# Commutator_Adaptor.net
KiCad netlist of a schematic drawn in EAGLE
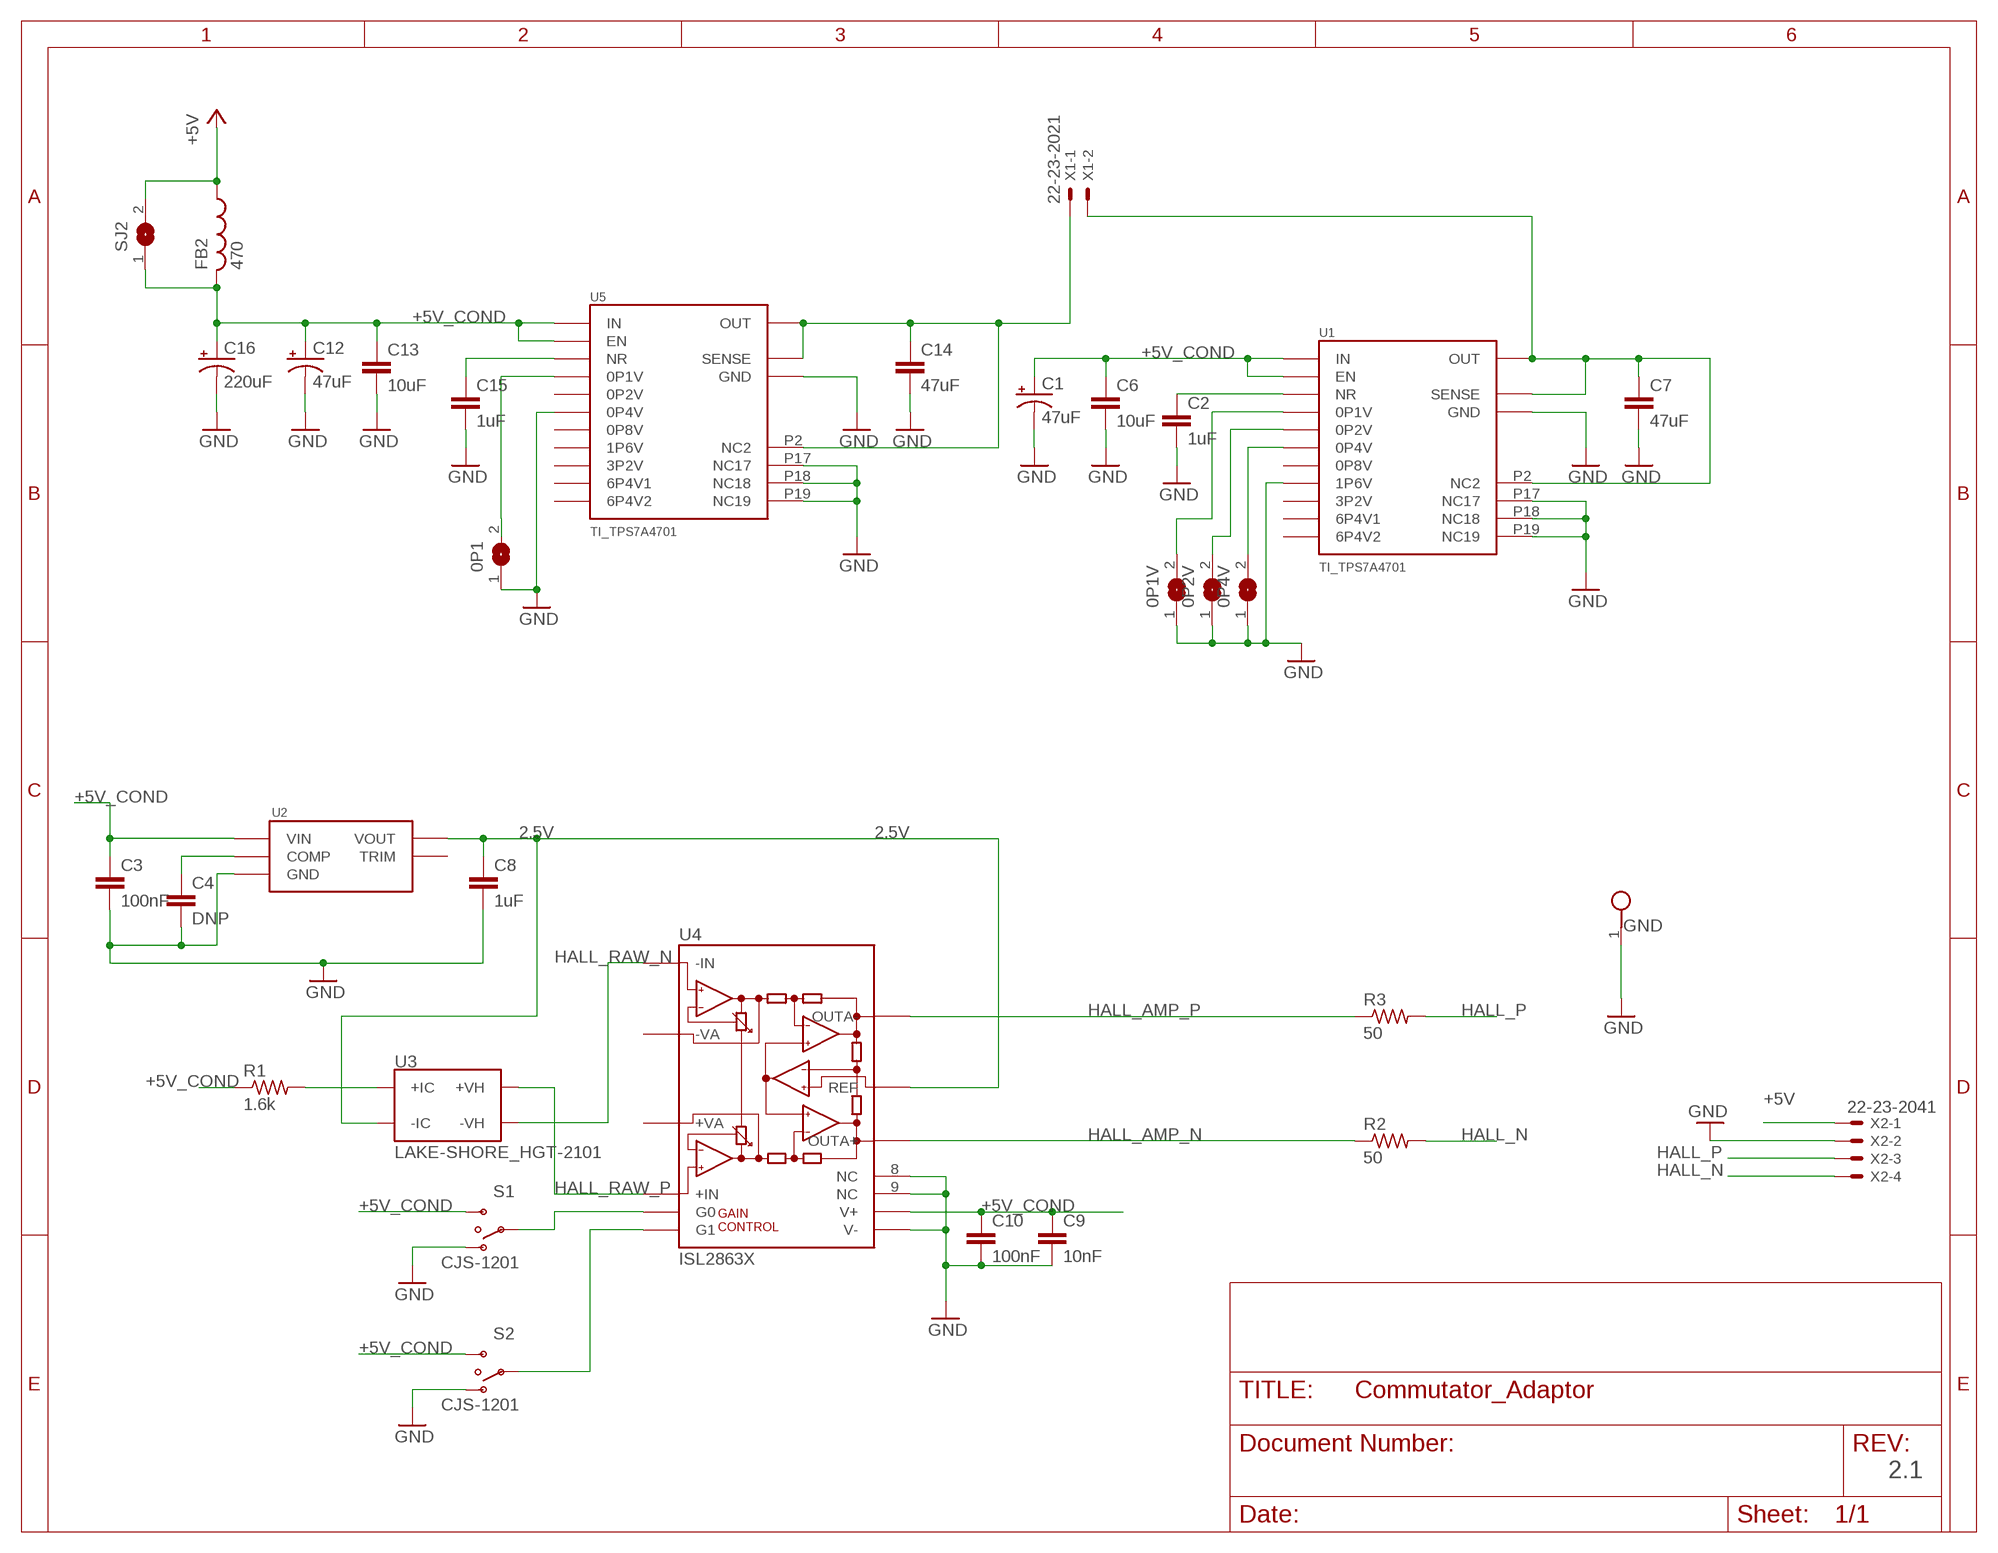
[diagram p0: schematic, sheet 1]

(export (version "E")
  (design (tool "Eeschema 10.0.6"))
  (components
    (comp (ref "0P1") (value "SJ") (footprint "eagle-import:SJ") (libsource (lib "eagle-import") (part "SJ")))
    (comp (ref "0P1V")
      (value "SJ")
      (footprint "eagle-import:SJ")
      (libsource (lib "eagle-import") (part "SJ"))
    )
    (comp (ref "0P2V")
      (value "SJ")
      (footprint "eagle-import:SJ")
      (libsource (lib "eagle-import") (part "SJ"))
    )
    (comp (ref "0P4V")
      (value "SJ")
      (footprint "eagle-import:SJ")
      (libsource (lib "eagle-import") (part "SJ"))
    )
    (comp (ref "C1")
      (value "47uF")
      (footprint "eagle-import:1210POL")
      (libsource (lib "eagle-import") (part "CPOL1210"))
    )
    (comp (ref "C2")
      (value "1uF")
      (footprint "eagle-import:0603")
      (libsource (lib "eagle-import") (part "C_0603"))
    )
    (comp (ref "C3")
      (value "100nF")
      (footprint "eagle-import:0402")
      (libsource (lib "eagle-import") (part "C_0402"))
    )
    (comp (ref "C4")
      (value "DNP")
      (footprint "eagle-import:0402")
      (libsource (lib "eagle-import") (part "C_0402"))
    )
    (comp (ref "C6")
      (value "10uF")
      (footprint "eagle-import:0805")
      (libsource (lib "eagle-import") (part "C_0805"))
    )
    (comp (ref "C7")
      (value "47uF")
      (footprint "eagle-import:1210")
      (libsource (lib "eagle-import") (part "C_1210"))
    )
    (comp (ref "C8")
      (value "1uF")
      (footprint "eagle-import:0603")
      (libsource (lib "eagle-import") (part "C_0603"))
    )
    (comp (ref "C9")
      (value "10nF")
      (footprint "eagle-import:0402")
      (libsource (lib "eagle-import") (part "C_0402"))
    )
    (comp (ref "C10")
      (value "100nF")
      (footprint "eagle-import:0402")
      (libsource (lib "eagle-import") (part "C_0402"))
    )
    (comp (ref "C12")
      (value "47uF")
      (footprint "eagle-import:1210POL")
      (libsource (lib "eagle-import") (part "CPOL1210"))
    )
    (comp (ref "C13")
      (value "10uF")
      (footprint "eagle-import:0805")
      (libsource (lib "eagle-import") (part "C_0805"))
    )
    (comp (ref "C14")
      (value "47uF")
      (footprint "eagle-import:1210")
      (libsource (lib "eagle-import") (part "C_1210"))
    )
    (comp (ref "C15")
      (value "1uF")
      (footprint "eagle-import:0603")
      (libsource (lib "eagle-import") (part "C_0603"))
    )
    (comp (ref "C16")
      (value "220uF")
      (footprint "eagle-import:JA0")
      (libsource (lib "eagle-import") (part "CPOL_JA0"))
    )
    (comp (ref "FB2")
      (value "470")
      (footprint "eagle-import:0603")
      (libsource (lib "eagle-import") (part "L_0603"))
    )
    (comp (ref "GND")
      (value "TESTPOINT_SMALL")
      (footprint "eagle-import:TESTPOINT_SMALL")
      (libsource (lib "eagle-import") (part "TESTPOINT_SMALL"))
    )
    (comp (ref "R1")
      (value "1.6k")
      (footprint "eagle-import:0402")
      (libsource (lib "eagle-import") (part "R_0402"))
    )
    (comp (ref "R2")
      (value "50")
      (footprint "eagle-import:0402")
      (libsource (lib "eagle-import") (part "R_0402"))
    )
    (comp (ref "R3")
      (value "50")
      (footprint "eagle-import:0402")
      (libsource (lib "eagle-import") (part "R_0402"))
    )
    (comp (ref "S1")
      (value "CJS-1201")
      (footprint "eagle-import:CJS-1201A1")
      (libsource (lib "eagle-import") (part "CJS-1201"))
    )
    (comp (ref "S2")
      (value "CJS-1201")
      (footprint "eagle-import:CJS-1201A1")
      (libsource (lib "eagle-import") (part "CJS-1201"))
    )
    (comp (ref "SJ2") (value "SJ") (footprint "eagle-import:SJ") (libsource (lib "eagle-import") (part "SJ")))
    (comp (ref "U1")
      (value "TI_TPS7A4701")
      (footprint "eagle-import:20-VQFN(5X5)")
      (libsource (lib "eagle-import") (part "TI_TPS7A4701"))
    )
    (comp (ref "U2")
      (value "ISL21090")
      (footprint "eagle-import:SO08")
      (libsource (lib "eagle-import") (part "ISL21090"))
    )
    (comp (ref "U3")
      (value "LAKE-SHORE_HGT-2101")
      (footprint "eagle-import:HGT-2101-SIDE")
      (libsource (lib "eagle-import") (part "LAKE-SHORE_HGT-2101"))
    )
    (comp (ref "U4")
      (value "ISL2863X")
      (footprint "eagle-import:TSSOP14")
      (libsource (lib "eagle-import") (part "ISL2863X"))
    )
    (comp (ref "U5")
      (value "TI_TPS7A4701")
      (footprint "eagle-import:20-VQFN(5X5)")
      (libsource (lib "eagle-import") (part "TI_TPS7A4701"))
    )
    (comp (ref "X1")
      (value "22-23-2021")
      (footprint "eagle-import:22-23-2021")
      (fields (field (name "MF") "MOLEX"))
      (libsource (lib "eagle-import") (part "22-23-2021"))
    )
    (comp (ref "X2")
      (value "22-23-2041")
      (footprint "eagle-import:22-23-2041")
      (fields (field (name "MF") "MOLEX"))
      (libsource (lib "eagle-import") (part "22-23-2041"))
    )
  )
  (nets
    (net (code "1") (name "+5V") (class "Default")
      (node (ref "FB2") (pin "1") (pinfunction "1_1") (pintype "passive"))
      (node (ref "SJ2") (pin "2") (pinfunction "2_2") (pintype "passive"))
      (node (ref "X2") (pin "1") (pinfunction "S_1") (pintype "passive"))
    )
    (net (code "2") (name "/+5V_COND") (class "Default")
      (node (ref "C1") (pin "POS") (pinfunction "+_POS") (pintype "passive"))
      (node (ref "C10") (pin "1") (pinfunction "1_1") (pintype "passive"))
      (node (ref "C12") (pin "POS") (pinfunction "+_POS") (pintype "passive"))
      (node (ref "C13") (pin "1") (pinfunction "1_1") (pintype "passive"))
      (node (ref "C16") (pin "POS") (pinfunction "+_POS") (pintype "passive"))
      (node (ref "C3") (pin "1") (pinfunction "1_1") (pintype "passive"))
      (node (ref "C6") (pin "1") (pinfunction "1_1") (pintype "passive"))
      (node (ref "C9") (pin "1") (pinfunction "1_1") (pintype "passive"))
      (node (ref "FB2") (pin "2") (pinfunction "2_2") (pintype "passive"))
      (node (ref "R1") (pin "1") (pinfunction "1_1") (pintype "passive"))
      (node (ref "S1") (pin "P$3") (pinfunction "S_P$3") (pintype "passive"))
      (node (ref "S2") (pin "P$3") (pinfunction "S_P$3") (pintype "passive"))
      (node (ref "SJ2") (pin "1") (pinfunction "1_1") (pintype "passive"))
      (node (ref "U1") (pin "P13") (pinfunction "EN_P13") (pintype "input"))
      (node (ref "U1") (pin "P15") (pinfunction "IN_P15") (pintype "power_in"))
      (node (ref "U1") (pin "P16") (pinfunction "IN_P16") (pintype "power_in"))
      (node (ref "U2") (pin "2") (pinfunction "VIN_2") (pintype "power_in"))
      (node (ref "U4") (pin "14") (pinfunction "V+_14") (pintype "power_in"))
      (node (ref "U5") (pin "P13") (pinfunction "EN_P13") (pintype "input"))
      (node (ref "U5") (pin "P15") (pinfunction "IN_P15") (pintype "power_in"))
      (node (ref "U5") (pin "P16") (pinfunction "IN_P16") (pintype "power_in"))
    )
    (net (code "3") (name "/2.5V") (class "Default")
      (node (ref "C8") (pin "1") (pinfunction "1_1") (pintype "passive"))
      (node (ref "U2") (pin "6") (pinfunction "VOUT_6") (pintype "power_in"))
      (node (ref "U3") (pin "PIN1") (pinfunction "-IC_PIN1") (pintype "power_in"))
      (node (ref "U4") (pin "11") (pinfunction "REF_11") (pintype "input"))
    )
    (net (code "4") (name "/HALL_AMP_N") (class "Default")
      (node (ref "R2") (pin "1") (pinfunction "1_1") (pintype "passive"))
      (node (ref "U4") (pin "12") (pinfunction "OUTA+_12") (pintype "passive"))
    )
    (net (code "5") (name "/HALL_AMP_P") (class "Default")
      (node (ref "R3") (pin "1") (pinfunction "1_1") (pintype "passive"))
      (node (ref "U4") (pin "10") (pinfunction "OUTA-_10") (pintype "output"))
    )
    (net (code "6") (name "/HALL_N") (class "Default")
      (node (ref "R2") (pin "2") (pinfunction "2_2") (pintype "passive"))
      (node (ref "X2") (pin "4") (pinfunction "S_4") (pintype "passive"))
    )
    (net (code "7") (name "/HALL_P") (class "Default")
      (node (ref "R3") (pin "2") (pinfunction "2_2") (pintype "passive"))
      (node (ref "X2") (pin "3") (pinfunction "S_3") (pintype "passive"))
    )
    (net (code "8") (name "/HALL_RAW_N") (class "Default")
      (node (ref "U3") (pin "WIRE1") (pinfunction "-VH_WIRE1") (pintype "output"))
      (node (ref "U4") (pin "5") (pinfunction "-IN_5") (pintype "input"))
    )
    (net (code "9") (name "/HALL_RAW_P") (class "Default")
      (node (ref "U3") (pin "PIN2") (pinfunction "+VH_PIN2") (pintype "output"))
      (node (ref "U4") (pin "4") (pinfunction "+IN_4") (pintype "input"))
    )
    (net (code "10") (name "GND") (class "Default")
      (node (ref "0P1") (pin "1") (pinfunction "1_1") (pintype "passive"))
      (node (ref "0P1V") (pin "1") (pinfunction "1_1") (pintype "passive"))
      (node (ref "0P2V") (pin "1") (pinfunction "1_1") (pintype "passive"))
      (node (ref "0P4V") (pin "1") (pinfunction "1_1") (pintype "passive"))
      (node (ref "C1") (pin "NEG") (pinfunction "-_NEG") (pintype "passive"))
      (node (ref "C10") (pin "2") (pinfunction "2_2") (pintype "passive"))
      (node (ref "C12") (pin "NEG") (pinfunction "-_NEG") (pintype "passive"))
      (node (ref "C13") (pin "2") (pinfunction "2_2") (pintype "passive"))
      (node (ref "C14") (pin "NEG") (pinfunction "2_NEG") (pintype "passive"))
      (node (ref "C15") (pin "2") (pinfunction "2_2") (pintype "passive"))
      (node (ref "C16") (pin "NEG") (pinfunction "-_NEG") (pintype "passive"))
      (node (ref "C2") (pin "2") (pinfunction "2_2") (pintype "passive"))
      (node (ref "C3") (pin "2") (pinfunction "2_2") (pintype "passive"))
      (node (ref "C4") (pin "2") (pinfunction "2_2") (pintype "passive"))
      (node (ref "C6") (pin "2") (pinfunction "2_2") (pintype "passive"))
      (node (ref "C7") (pin "NEG") (pinfunction "2_NEG") (pintype "passive"))
      (node (ref "C8") (pin "2") (pinfunction "2_2") (pintype "passive"))
      (node (ref "C9") (pin "2") (pinfunction "2_2") (pintype "passive"))
      (node (ref "GND") (pin "1") (pinfunction "1_1") (pintype "passive"))
      (node (ref "S1") (pin "P$1") (pinfunction "O_P$1") (pintype "passive"))
      (node (ref "S2") (pin "P$1") (pinfunction "O_P$1") (pintype "passive"))
      (node (ref "U1") (pin "P17") (pinfunction "NC17_P17") (pintype "passive"))
      (node (ref "U1") (pin "P18") (pinfunction "NC18_P18") (pintype "passive"))
      (node (ref "U1") (pin "P19") (pinfunction "NC19_P19") (pintype "passive"))
      (node (ref "U1") (pin "P7") (pinfunction "GND_P7") (pintype "power_in"))
      (node (ref "U1") (pin "P8") (pinfunction "1P6V_P8") (pintype "passive"))
      (node (ref "U1") (pin "THERMAL@1") (pinfunction "GND_THERMAL@1") (pintype "power_in"))
      (node (ref "U1") (pin "THERMAL@10") (pinfunction "GND_THERMAL@10") (pintype "power_in"))
      (node (ref "U1") (pin "THERMAL@2") (pinfunction "GND_THERMAL@2") (pintype "power_in"))
      (node (ref "U1") (pin "THERMAL@3") (pinfunction "GND_THERMAL@3") (pintype "power_in"))
      (node (ref "U1") (pin "THERMAL@4") (pinfunction "GND_THERMAL@4") (pintype "power_in"))
      (node (ref "U1") (pin "THERMAL@5") (pinfunction "GND_THERMAL@5") (pintype "power_in"))
      (node (ref "U1") (pin "THERMAL@6") (pinfunction "GND_THERMAL@6") (pintype "power_in"))
      (node (ref "U1") (pin "THERMAL@7") (pinfunction "GND_THERMAL@7") (pintype "power_in"))
      (node (ref "U1") (pin "THERMAL@8") (pinfunction "GND_THERMAL@8") (pintype "power_in"))
      (node (ref "U1") (pin "THERMAL@9") (pinfunction "GND_THERMAL@9") (pintype "power_in"))
      (node (ref "U2") (pin "4") (pinfunction "GND_4") (pintype "power_in"))
      (node (ref "U4") (pin "7") (pinfunction "V-_7") (pintype "power_in"))
      (node (ref "U4") (pin "8") (pinfunction "NC_8") (pintype "passive"))
      (node (ref "U4") (pin "9") (pinfunction "NC_9") (pintype "passive"))
      (node (ref "U5") (pin "P10") (pinfunction "0P4V_P10") (pintype "passive"))
      (node (ref "U5") (pin "P17") (pinfunction "NC17_P17") (pintype "passive"))
      (node (ref "U5") (pin "P18") (pinfunction "NC18_P18") (pintype "passive"))
      (node (ref "U5") (pin "P19") (pinfunction "NC19_P19") (pintype "passive"))
      (node (ref "U5") (pin "P7") (pinfunction "GND_P7") (pintype "power_in"))
      (node (ref "U5") (pin "THERMAL@1") (pinfunction "GND_THERMAL@1") (pintype "power_in"))
      (node (ref "U5") (pin "THERMAL@10") (pinfunction "GND_THERMAL@10") (pintype "power_in"))
      (node (ref "U5") (pin "THERMAL@2") (pinfunction "GND_THERMAL@2") (pintype "power_in"))
      (node (ref "U5") (pin "THERMAL@3") (pinfunction "GND_THERMAL@3") (pintype "power_in"))
      (node (ref "U5") (pin "THERMAL@4") (pinfunction "GND_THERMAL@4") (pintype "power_in"))
      (node (ref "U5") (pin "THERMAL@5") (pinfunction "GND_THERMAL@5") (pintype "power_in"))
      (node (ref "U5") (pin "THERMAL@6") (pinfunction "GND_THERMAL@6") (pintype "power_in"))
      (node (ref "U5") (pin "THERMAL@7") (pinfunction "GND_THERMAL@7") (pintype "power_in"))
      (node (ref "U5") (pin "THERMAL@8") (pinfunction "GND_THERMAL@8") (pintype "power_in"))
      (node (ref "U5") (pin "THERMAL@9") (pinfunction "GND_THERMAL@9") (pintype "power_in"))
      (node (ref "X2") (pin "2") (pinfunction "S_2") (pintype "passive"))
    )
    (net (code "11") (name "Net-(C7-1)") (class "Default")
      (node (ref "C7") (pin "POS") (pinfunction "1_POS") (pintype "passive"))
      (node (ref "U1") (pin "P1") (pinfunction "OUT_P1") (pintype "power_in"))
      (node (ref "U1") (pin "P2") (pinfunction "NC2_P2") (pintype "passive"))
      (node (ref "U1") (pin "P20") (pinfunction "OUT_P20") (pintype "power_in"))
      (node (ref "U1") (pin "P3") (pinfunction "SENSE_P3") (pintype "input"))
      (node (ref "X1") (pin "2") (pinfunction "S_2") (pintype "passive"))
    )
    (net (code "12") (name "Net-(C14-1)") (class "Default")
      (node (ref "C14") (pin "POS") (pinfunction "1_POS") (pintype "passive"))
      (node (ref "U5") (pin "P1") (pinfunction "OUT_P1") (pintype "power_in"))
      (node (ref "U5") (pin "P2") (pinfunction "NC2_P2") (pintype "passive"))
      (node (ref "U5") (pin "P20") (pinfunction "OUT_P20") (pintype "power_in"))
      (node (ref "U5") (pin "P3") (pinfunction "SENSE_P3") (pintype "input"))
      (node (ref "X1") (pin "1") (pinfunction "S_1") (pintype "passive"))
    )
    (net (code "13") (name "Net-(S1-P)") (class "Default")
      (node (ref "S1") (pin "P$2") (pinfunction "P_P$2") (pintype "passive"))
      (node (ref "U4") (pin "1") (pinfunction "G0_1") (pintype "input"))
    )
    (net (code "14") (name "Net-(S2-P)") (class "Default")
      (node (ref "S2") (pin "P$2") (pinfunction "P_P$2") (pintype "passive"))
      (node (ref "U4") (pin "2") (pinfunction "G1_2") (pintype "input"))
    )
    (net (code "15") (name "Net-(U1-0P1V)") (class "Default")
      (node (ref "0P1V") (pin "2") (pinfunction "2_2") (pintype "passive"))
      (node (ref "U1") (pin "P12") (pinfunction "0P1V_P12") (pintype "passive"))
    )
    (net (code "16") (name "Net-(U1-0P2V)") (class "Default")
      (node (ref "0P2V") (pin "2") (pinfunction "2_2") (pintype "passive"))
      (node (ref "U1") (pin "P11") (pinfunction "0P2V_P11") (pintype "passive"))
    )
    (net (code "17") (name "Net-(U1-0P4V)") (class "Default")
      (node (ref "0P4V") (pin "2") (pinfunction "2_2") (pintype "passive"))
      (node (ref "U1") (pin "P10") (pinfunction "0P4V_P10") (pintype "passive"))
    )
    (net (code "18") (name "Net-(U1-NR)") (class "Default")
      (node (ref "C2") (pin "1") (pinfunction "1_1") (pintype "passive"))
      (node (ref "U1") (pin "P14") (pinfunction "NR_P14") (pintype "passive"))
    )
    (net (code "19") (name "Net-(U2-COMP)") (class "Default")
      (node (ref "C4") (pin "1") (pinfunction "1_1") (pintype "passive"))
      (node (ref "U2") (pin "3") (pinfunction "COMP_3") (pintype "output"))
    )
    (net (code "20") (name "Net-(U3-+IC)") (class "Default")
      (node (ref "R1") (pin "2") (pinfunction "2_2") (pintype "passive"))
      (node (ref "U3") (pin "WIRE2") (pinfunction "+IC_WIRE2") (pintype "power_in"))
    )
    (net (code "21") (name "Net-(U5-0P1V)") (class "Default")
      (node (ref "0P1") (pin "2") (pinfunction "2_2") (pintype "passive"))
      (node (ref "U5") (pin "P12") (pinfunction "0P1V_P12") (pintype "passive"))
    )
    (net (code "22") (name "Net-(U5-NR)") (class "Default")
      (node (ref "C15") (pin "1") (pinfunction "1_1") (pintype "passive"))
      (node (ref "U5") (pin "P14") (pinfunction "NR_P14") (pintype "passive"))
    )
    (net (code "23") (name "unconnected-(U1-0P8V-PadP9)") (class "Default")
      (node (ref "U1") (pin "P9") (pinfunction "0P8V_P9") (pintype "passive"))
    )
    (net (code "24") (name "unconnected-(U1-3P2V-PadP6)") (class "Default")
      (node (ref "U1") (pin "P6") (pinfunction "3P2V_P6") (pintype "passive"))
    )
    (net (code "25") (name "unconnected-(U1-6P4V1-PadP5)") (class "Default")
      (node (ref "U1") (pin "P5") (pinfunction "6P4V1_P5") (pintype "passive"))
    )
    (net (code "26") (name "unconnected-(U1-6P4V2-PadP4)") (class "Default")
      (node (ref "U1") (pin "P4") (pinfunction "6P4V2_P4") (pintype "passive"))
    )
    (net (code "27") (name "unconnected-(U2-TRIM-Pad5)") (class "Default")
      (node (ref "U2") (pin "5") (pinfunction "TRIM_5") (pintype "passive"))
    )
    (net (code "28") (name "unconnected-(U4-+VA-Pad6)") (class "Default")
      (node (ref "U4") (pin "6") (pinfunction "+VA_6") (pintype "output"))
    )
    (net (code "29") (name "unconnected-(U4--VA-Pad3)") (class "Default")
      (node (ref "U4") (pin "3") (pinfunction "-VA_3") (pintype "output"))
    )
    (net (code "30") (name "unconnected-(U5-0P2V-PadP11)") (class "Default")
      (node (ref "U5") (pin "P11") (pinfunction "0P2V_P11") (pintype "passive"))
    )
    (net (code "31") (name "unconnected-(U5-0P8V-PadP9)") (class "Default")
      (node (ref "U5") (pin "P9") (pinfunction "0P8V_P9") (pintype "passive"))
    )
    (net (code "32") (name "unconnected-(U5-1P6V-PadP8)") (class "Default")
      (node (ref "U5") (pin "P8") (pinfunction "1P6V_P8") (pintype "passive"))
    )
    (net (code "33") (name "unconnected-(U5-3P2V-PadP6)") (class "Default")
      (node (ref "U5") (pin "P6") (pinfunction "3P2V_P6") (pintype "passive"))
    )
    (net (code "34") (name "unconnected-(U5-6P4V1-PadP5)") (class "Default")
      (node (ref "U5") (pin "P5") (pinfunction "6P4V1_P5") (pintype "passive"))
    )
    (net (code "35") (name "unconnected-(U5-6P4V2-PadP4)") (class "Default")
      (node (ref "U5") (pin "P4") (pinfunction "6P4V2_P4") (pintype "passive"))
    )
  )
)
